# mt15_c.net
KiCad netlist of a schematic drawn in EAGLE
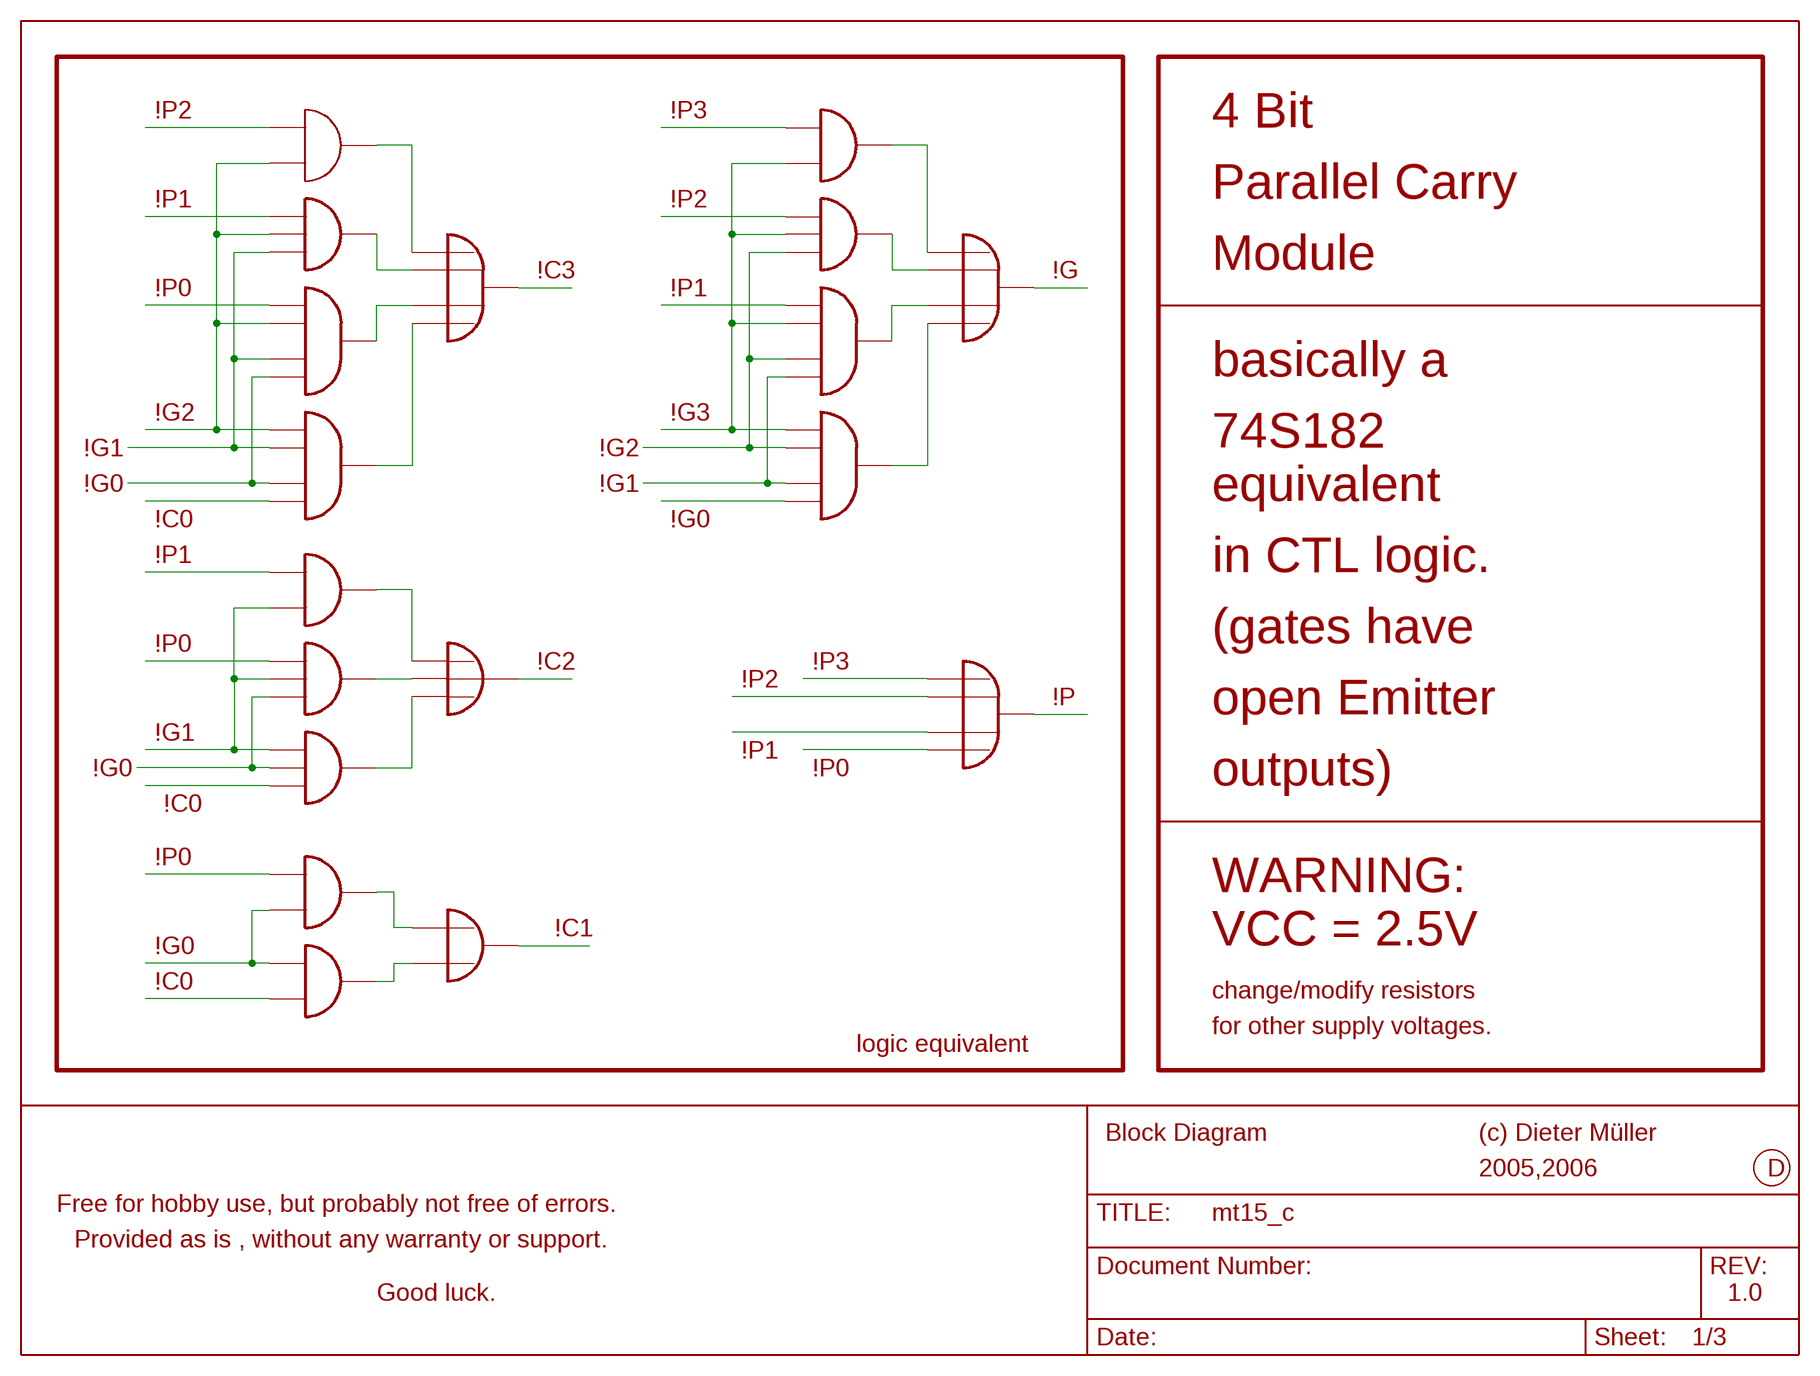
[diagram p0: schematic, sheet 1]
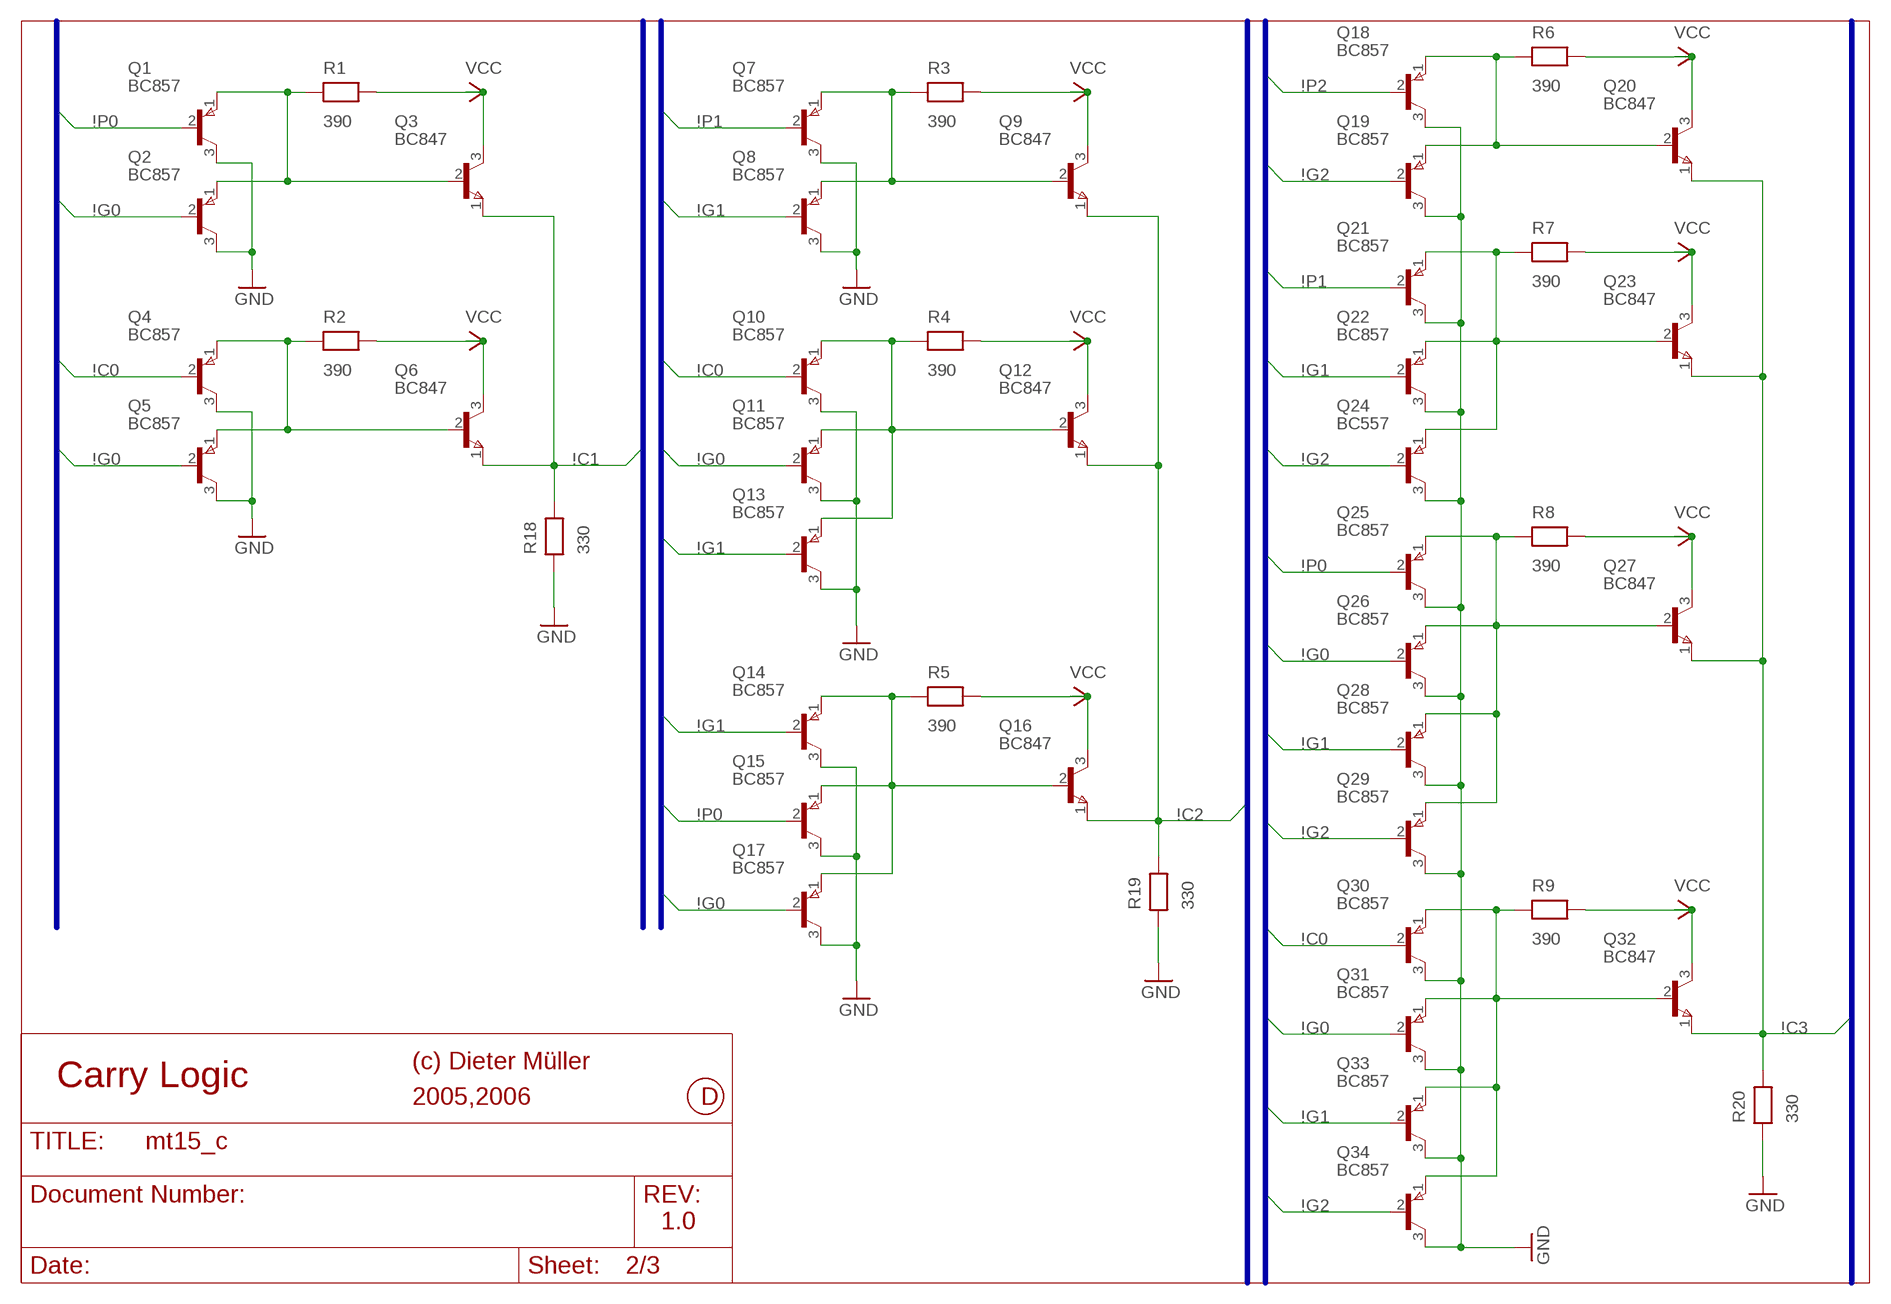
[diagram p1: schematic, sheet 2]
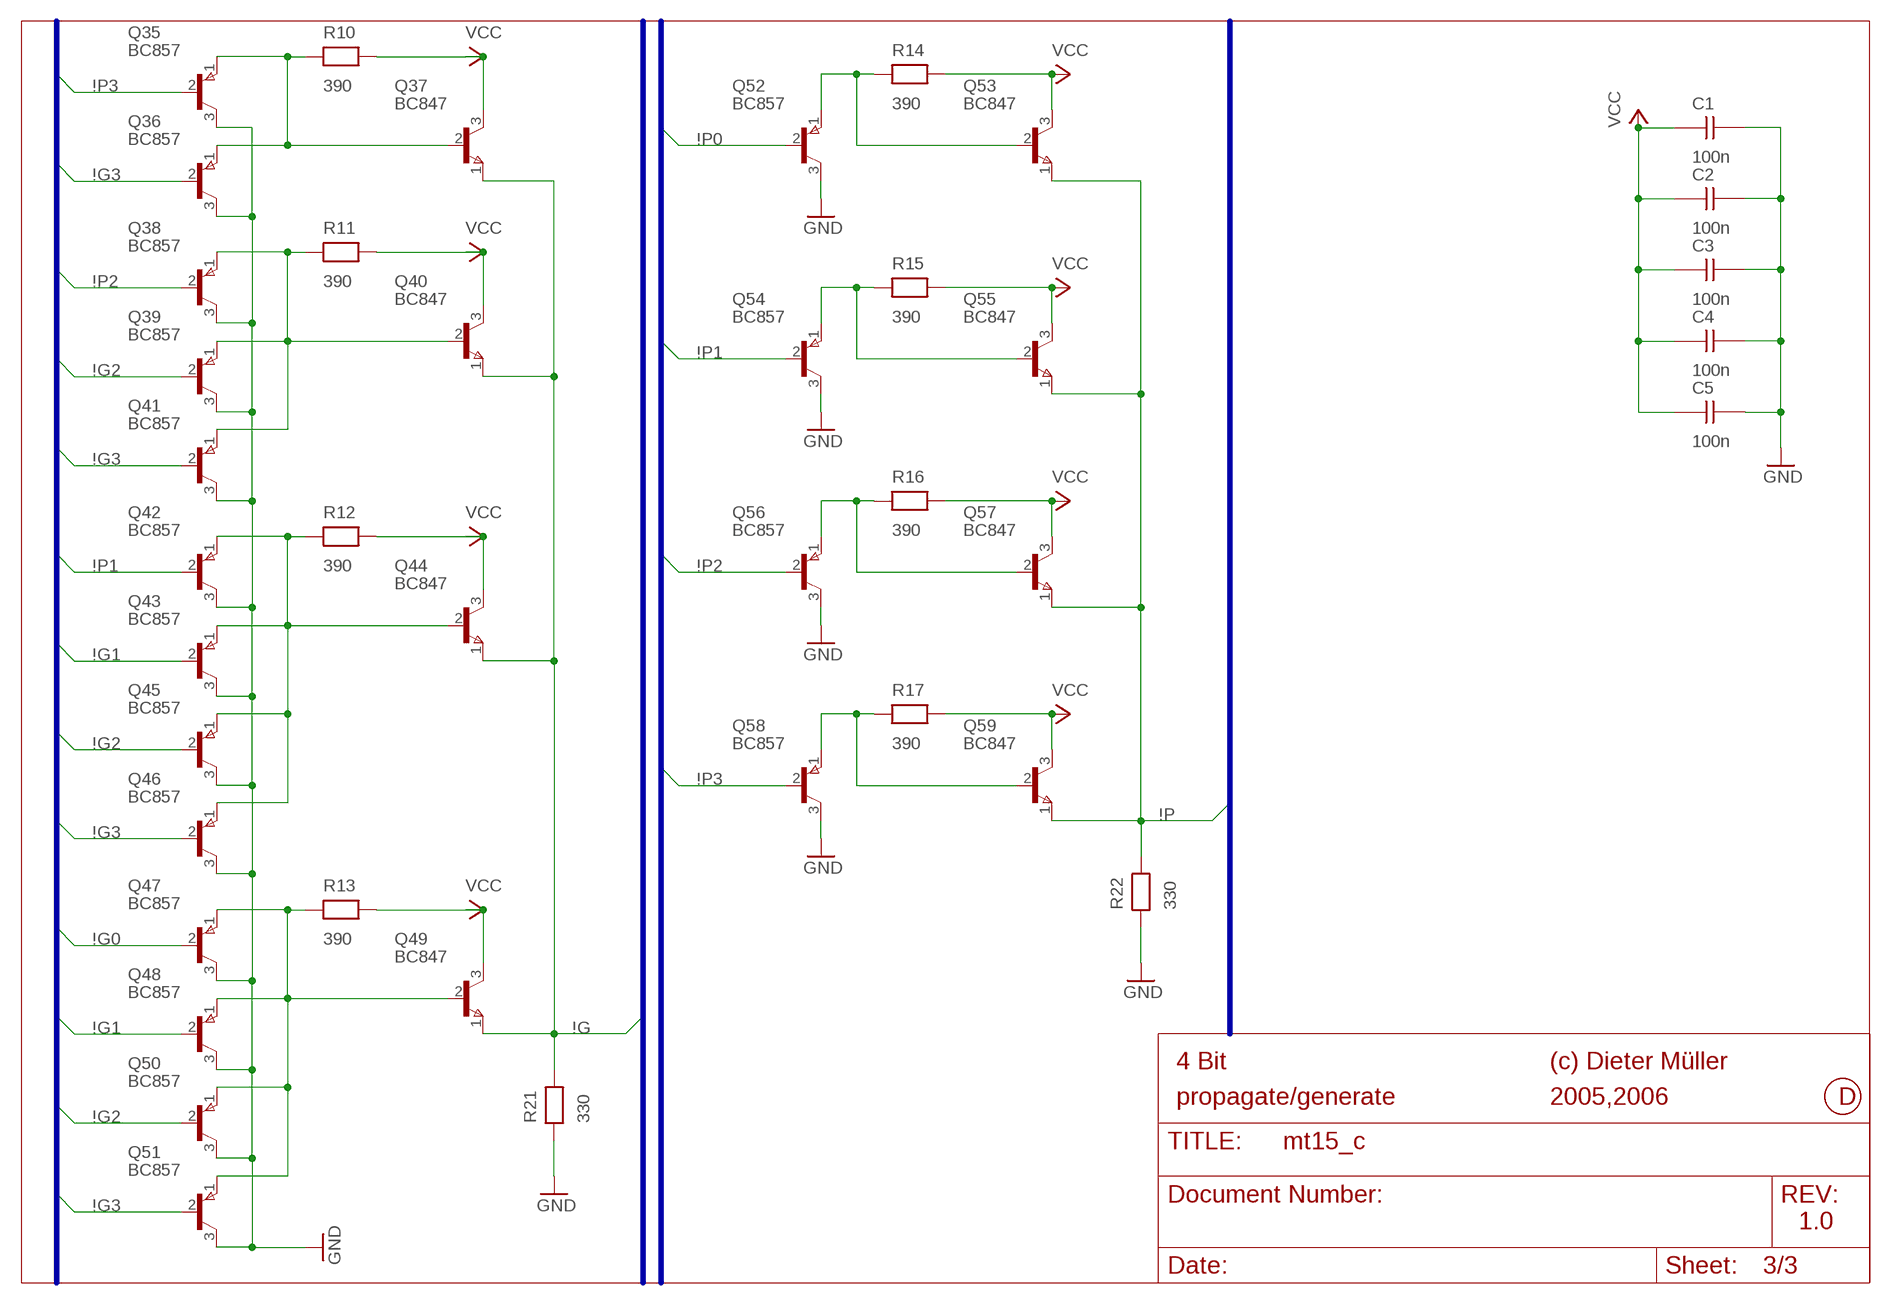
[diagram p2: schematic, sheet 3]

(export (version "E")
  (design (tool "Eeschema 10.0.6"))
  (components
    (comp (ref "Q1")
      (value "BC857")
      (footprint "eagle-import:SOT-23")
      (libsource (lib "eagle-import") (part "BC557@2"))
    )
    (comp (ref "Q2")
      (value "BC857")
      (footprint "eagle-import:SOT-23")
      (libsource (lib "eagle-import") (part "BC557@2"))
    )
    (comp (ref "Q3")
      (value "BC847")
      (footprint "eagle-import:SOT-23")
      (libsource (lib "eagle-import") (part "BC547@2"))
    )
    (comp (ref "Q4")
      (value "BC857")
      (footprint "eagle-import:SOT-23")
      (libsource (lib "eagle-import") (part "BC557@2"))
    )
    (comp (ref "Q5")
      (value "BC857")
      (footprint "eagle-import:SOT-23")
      (libsource (lib "eagle-import") (part "BC557@2"))
    )
    (comp (ref "Q6")
      (value "BC847")
      (footprint "eagle-import:SOT-23")
      (libsource (lib "eagle-import") (part "BC547@2"))
    )
    (comp (ref "Q7")
      (value "BC857")
      (footprint "eagle-import:SOT-23")
      (libsource (lib "eagle-import") (part "BC557@2"))
    )
    (comp (ref "Q8")
      (value "BC857")
      (footprint "eagle-import:SOT-23")
      (libsource (lib "eagle-import") (part "BC557@2"))
    )
    (comp (ref "Q9")
      (value "BC847")
      (footprint "eagle-import:SOT-23")
      (libsource (lib "eagle-import") (part "BC547@2"))
    )
    (comp (ref "Q10")
      (value "BC857")
      (footprint "eagle-import:SOT-23")
      (libsource (lib "eagle-import") (part "BC557@2"))
    )
    (comp (ref "Q11")
      (value "BC857")
      (footprint "eagle-import:SOT-23")
      (libsource (lib "eagle-import") (part "BC557@2"))
    )
    (comp (ref "Q12")
      (value "BC847")
      (footprint "eagle-import:SOT-23")
      (libsource (lib "eagle-import") (part "BC547@2"))
    )
    (comp (ref "Q13")
      (value "BC857")
      (footprint "eagle-import:SOT-23")
      (libsource (lib "eagle-import") (part "BC557@2"))
    )
    (comp (ref "Q14")
      (value "BC857")
      (footprint "eagle-import:SOT-23")
      (libsource (lib "eagle-import") (part "BC557@2"))
    )
    (comp (ref "Q15")
      (value "BC857")
      (footprint "eagle-import:SOT-23")
      (libsource (lib "eagle-import") (part "BC557@2"))
    )
    (comp (ref "Q16")
      (value "BC847")
      (footprint "eagle-import:SOT-23")
      (libsource (lib "eagle-import") (part "BC547@2"))
    )
    (comp (ref "Q17")
      (value "BC857")
      (footprint "eagle-import:SOT-23")
      (libsource (lib "eagle-import") (part "BC557@2"))
    )
    (comp (ref "Q18")
      (value "BC857")
      (footprint "eagle-import:SOT-23")
      (libsource (lib "eagle-import") (part "BC557@2"))
    )
    (comp (ref "Q19")
      (value "BC857")
      (footprint "eagle-import:SOT-23")
      (libsource (lib "eagle-import") (part "BC557@2"))
    )
    (comp (ref "Q20")
      (value "BC847")
      (footprint "eagle-import:SOT-23")
      (libsource (lib "eagle-import") (part "BC547@2"))
    )
    (comp (ref "Q21")
      (value "BC857")
      (footprint "eagle-import:SOT-23")
      (libsource (lib "eagle-import") (part "BC557@2"))
    )
    (comp (ref "Q22")
      (value "BC857")
      (footprint "eagle-import:SOT-23")
      (libsource (lib "eagle-import") (part "BC557@2"))
    )
    (comp (ref "Q23")
      (value "BC847")
      (footprint "eagle-import:SOT-23")
      (libsource (lib "eagle-import") (part "BC547@2"))
    )
    (comp (ref "Q24")
      (value "BC557")
      (footprint "eagle-import:SOT-23")
      (libsource (lib "eagle-import") (part "BC557@2"))
    )
    (comp (ref "Q25")
      (value "BC857")
      (footprint "eagle-import:SOT-23")
      (libsource (lib "eagle-import") (part "BC557@2"))
    )
    (comp (ref "Q26")
      (value "BC857")
      (footprint "eagle-import:SOT-23")
      (libsource (lib "eagle-import") (part "BC557@2"))
    )
    (comp (ref "Q27")
      (value "BC847")
      (footprint "eagle-import:SOT-23")
      (libsource (lib "eagle-import") (part "BC547@2"))
    )
    (comp (ref "Q28")
      (value "BC857")
      (footprint "eagle-import:SOT-23")
      (libsource (lib "eagle-import") (part "BC557@2"))
    )
    (comp (ref "Q29")
      (value "BC857")
      (footprint "eagle-import:SOT-23")
      (libsource (lib "eagle-import") (part "BC557@2"))
    )
    (comp (ref "Q30")
      (value "BC857")
      (footprint "eagle-import:SOT-23")
      (libsource (lib "eagle-import") (part "BC557@2"))
    )
    (comp (ref "Q31")
      (value "BC857")
      (footprint "eagle-import:SOT-23")
      (libsource (lib "eagle-import") (part "BC557@2"))
    )
    (comp (ref "Q32")
      (value "BC847")
      (footprint "eagle-import:SOT-23")
      (libsource (lib "eagle-import") (part "BC547@2"))
    )
    (comp (ref "Q33")
      (value "BC857")
      (footprint "eagle-import:SOT-23")
      (libsource (lib "eagle-import") (part "BC557@2"))
    )
    (comp (ref "Q34")
      (value "BC857")
      (footprint "eagle-import:SOT-23")
      (libsource (lib "eagle-import") (part "BC557@2"))
    )
    (comp (ref "R1")
      (value "390")
      (footprint "eagle-import:0204")
      (libsource (lib "eagle-import") (part "RESEU-7,5@2"))
    )
    (comp (ref "R2")
      (value "390")
      (footprint "eagle-import:0204")
      (libsource (lib "eagle-import") (part "RESEU-7,5@2"))
    )
    (comp (ref "R3")
      (value "390")
      (footprint "eagle-import:0204")
      (libsource (lib "eagle-import") (part "RESEU-7,5@2"))
    )
    (comp (ref "R4")
      (value "390")
      (footprint "eagle-import:0204")
      (libsource (lib "eagle-import") (part "RESEU-7,5@2"))
    )
    (comp (ref "R5")
      (value "390")
      (footprint "eagle-import:0204")
      (libsource (lib "eagle-import") (part "RESEU-7,5@2"))
    )
    (comp (ref "R6")
      (value "390")
      (footprint "eagle-import:0204")
      (libsource (lib "eagle-import") (part "RESEU-7,5@2"))
    )
    (comp (ref "R7")
      (value "390")
      (footprint "eagle-import:0204")
      (libsource (lib "eagle-import") (part "RESEU-7,5@2"))
    )
    (comp (ref "R8")
      (value "390")
      (footprint "eagle-import:0204")
      (libsource (lib "eagle-import") (part "RESEU-7,5@2"))
    )
    (comp (ref "R9")
      (value "390")
      (footprint "eagle-import:0204")
      (libsource (lib "eagle-import") (part "RESEU-7,5@2"))
    )
    (comp (ref "R18")
      (value "330")
      (footprint "eagle-import:0204")
      (libsource (lib "eagle-import") (part "RESEU-7,5@2"))
    )
    (comp (ref "R19")
      (value "330")
      (footprint "eagle-import:0204")
      (libsource (lib "eagle-import") (part "RESEU-7,5@2"))
    )
    (comp (ref "R20")
      (value "330")
      (footprint "eagle-import:0204")
      (libsource (lib "eagle-import") (part "RESEU-7,5@2"))
    )
    (comp (ref "C1")
      (value "100n")
      (footprint "eagle-import:0204")
      (libsource (lib "eagle-import") (part "CAPNP-5@2"))
    )
    (comp (ref "C2")
      (value "100n")
      (footprint "eagle-import:0204")
      (libsource (lib "eagle-import") (part "CAPNP-5@2"))
    )
    (comp (ref "C3")
      (value "100n")
      (footprint "eagle-import:0204")
      (libsource (lib "eagle-import") (part "CAPNP-5@2"))
    )
    (comp (ref "C4")
      (value "100n")
      (footprint "eagle-import:0204")
      (libsource (lib "eagle-import") (part "CAPNP-5@2"))
    )
    (comp (ref "C5")
      (value "100n")
      (footprint "eagle-import:0204")
      (libsource (lib "eagle-import") (part "CAPNP-5@2"))
    )
    (comp (ref "Q35")
      (value "BC857")
      (footprint "eagle-import:SOT-23")
      (libsource (lib "eagle-import") (part "BC557@2"))
    )
    (comp (ref "Q36")
      (value "BC857")
      (footprint "eagle-import:SOT-23")
      (libsource (lib "eagle-import") (part "BC557@2"))
    )
    (comp (ref "Q37")
      (value "BC847")
      (footprint "eagle-import:SOT-23")
      (libsource (lib "eagle-import") (part "BC547@2"))
    )
    (comp (ref "Q38")
      (value "BC857")
      (footprint "eagle-import:SOT-23")
      (libsource (lib "eagle-import") (part "BC557@2"))
    )
    (comp (ref "Q39")
      (value "BC857")
      (footprint "eagle-import:SOT-23")
      (libsource (lib "eagle-import") (part "BC557@2"))
    )
    (comp (ref "Q40")
      (value "BC847")
      (footprint "eagle-import:SOT-23")
      (libsource (lib "eagle-import") (part "BC547@2"))
    )
    (comp (ref "Q41")
      (value "BC857")
      (footprint "eagle-import:SOT-23")
      (libsource (lib "eagle-import") (part "BC557@2"))
    )
    (comp (ref "Q42")
      (value "BC857")
      (footprint "eagle-import:SOT-23")
      (libsource (lib "eagle-import") (part "BC557@2"))
    )
    (comp (ref "Q43")
      (value "BC857")
      (footprint "eagle-import:SOT-23")
      (libsource (lib "eagle-import") (part "BC557@2"))
    )
    (comp (ref "Q44")
      (value "BC847")
      (footprint "eagle-import:SOT-23")
      (libsource (lib "eagle-import") (part "BC547@2"))
    )
    (comp (ref "Q45")
      (value "BC857")
      (footprint "eagle-import:SOT-23")
      (libsource (lib "eagle-import") (part "BC557@2"))
    )
    (comp (ref "Q46")
      (value "BC857")
      (footprint "eagle-import:SOT-23")
      (libsource (lib "eagle-import") (part "BC557@2"))
    )
    (comp (ref "Q47")
      (value "BC857")
      (footprint "eagle-import:SOT-23")
      (libsource (lib "eagle-import") (part "BC557@2"))
    )
    (comp (ref "Q48")
      (value "BC857")
      (footprint "eagle-import:SOT-23")
      (libsource (lib "eagle-import") (part "BC557@2"))
    )
    (comp (ref "Q49")
      (value "BC847")
      (footprint "eagle-import:SOT-23")
      (libsource (lib "eagle-import") (part "BC547@2"))
    )
    (comp (ref "Q50")
      (value "BC857")
      (footprint "eagle-import:SOT-23")
      (libsource (lib "eagle-import") (part "BC557@2"))
    )
    (comp (ref "Q51")
      (value "BC857")
      (footprint "eagle-import:SOT-23")
      (libsource (lib "eagle-import") (part "BC557@2"))
    )
    (comp (ref "Q52")
      (value "BC857")
      (footprint "eagle-import:SOT-23")
      (libsource (lib "eagle-import") (part "BC557@2"))
    )
    (comp (ref "Q53")
      (value "BC847")
      (footprint "eagle-import:SOT-23")
      (libsource (lib "eagle-import") (part "BC547@2"))
    )
    (comp (ref "Q54")
      (value "BC857")
      (footprint "eagle-import:SOT-23")
      (libsource (lib "eagle-import") (part "BC557@2"))
    )
    (comp (ref "Q55")
      (value "BC847")
      (footprint "eagle-import:SOT-23")
      (libsource (lib "eagle-import") (part "BC547@2"))
    )
    (comp (ref "Q56")
      (value "BC857")
      (footprint "eagle-import:SOT-23")
      (libsource (lib "eagle-import") (part "BC557@2"))
    )
    (comp (ref "Q57")
      (value "BC847")
      (footprint "eagle-import:SOT-23")
      (libsource (lib "eagle-import") (part "BC547@2"))
    )
    (comp (ref "Q58")
      (value "BC857")
      (footprint "eagle-import:SOT-23")
      (libsource (lib "eagle-import") (part "BC557@2"))
    )
    (comp (ref "Q59")
      (value "BC847")
      (footprint "eagle-import:SOT-23")
      (libsource (lib "eagle-import") (part "BC547@2"))
    )
    (comp (ref "R10")
      (value "390")
      (footprint "eagle-import:0204")
      (libsource (lib "eagle-import") (part "RESEU-7,5@2"))
    )
    (comp (ref "R11")
      (value "390")
      (footprint "eagle-import:0204")
      (libsource (lib "eagle-import") (part "RESEU-7,5@2"))
    )
    (comp (ref "R12")
      (value "390")
      (footprint "eagle-import:0204")
      (libsource (lib "eagle-import") (part "RESEU-7,5@2"))
    )
    (comp (ref "R13")
      (value "390")
      (footprint "eagle-import:0204")
      (libsource (lib "eagle-import") (part "RESEU-7,5@2"))
    )
    (comp (ref "R14")
      (value "390")
      (footprint "eagle-import:0204")
      (libsource (lib "eagle-import") (part "RESEU-7,5@2"))
    )
    (comp (ref "R15")
      (value "390")
      (footprint "eagle-import:0204")
      (libsource (lib "eagle-import") (part "RESEU-7,5@2"))
    )
    (comp (ref "R16")
      (value "390")
      (footprint "eagle-import:0204")
      (libsource (lib "eagle-import") (part "RESEU-7,5@2"))
    )
    (comp (ref "R17")
      (value "390")
      (footprint "eagle-import:0204")
      (libsource (lib "eagle-import") (part "RESEU-7,5@2"))
    )
    (comp (ref "R21")
      (value "330")
      (footprint "eagle-import:0204")
      (libsource (lib "eagle-import") (part "RESEU-7,5@2"))
    )
    (comp (ref "R22")
      (value "330")
      (footprint "eagle-import:0204")
      (libsource (lib "eagle-import") (part "RESEU-7,5@2"))
    )
  )
  (nets
    (net (code "1") (name "GND") (class "Default")
      (node (ref "C1") (pin "2") (pinfunction "2_2") (pintype "passive"))
      (node (ref "C2") (pin "2") (pinfunction "2_2") (pintype "passive"))
      (node (ref "C3") (pin "2") (pinfunction "2_2") (pintype "passive"))
      (node (ref "C4") (pin "2") (pinfunction "2_2") (pintype "passive"))
      (node (ref "C5") (pin "2") (pinfunction "2_2") (pintype "passive"))
      (node (ref "Q1") (pin "3") (pinfunction "C_3") (pintype "passive"))
      (node (ref "Q10") (pin "3") (pinfunction "C_3") (pintype "passive"))
      (node (ref "Q11") (pin "3") (pinfunction "C_3") (pintype "passive"))
      (node (ref "Q13") (pin "3") (pinfunction "C_3") (pintype "passive"))
      (node (ref "Q14") (pin "3") (pinfunction "C_3") (pintype "passive"))
      (node (ref "Q15") (pin "3") (pinfunction "C_3") (pintype "passive"))
      (node (ref "Q17") (pin "3") (pinfunction "C_3") (pintype "passive"))
      (node (ref "Q18") (pin "3") (pinfunction "C_3") (pintype "passive"))
      (node (ref "Q19") (pin "3") (pinfunction "C_3") (pintype "passive"))
      (node (ref "Q2") (pin "3") (pinfunction "C_3") (pintype "passive"))
      (node (ref "Q21") (pin "3") (pinfunction "C_3") (pintype "passive"))
      (node (ref "Q22") (pin "3") (pinfunction "C_3") (pintype "passive"))
      (node (ref "Q24") (pin "3") (pinfunction "C_3") (pintype "passive"))
      (node (ref "Q25") (pin "3") (pinfunction "C_3") (pintype "passive"))
      (node (ref "Q26") (pin "3") (pinfunction "C_3") (pintype "passive"))
      (node (ref "Q28") (pin "3") (pinfunction "C_3") (pintype "passive"))
      (node (ref "Q29") (pin "3") (pinfunction "C_3") (pintype "passive"))
      (node (ref "Q30") (pin "3") (pinfunction "C_3") (pintype "passive"))
      (node (ref "Q31") (pin "3") (pinfunction "C_3") (pintype "passive"))
      (node (ref "Q33") (pin "3") (pinfunction "C_3") (pintype "passive"))
      (node (ref "Q34") (pin "3") (pinfunction "C_3") (pintype "passive"))
      (node (ref "Q35") (pin "3") (pinfunction "C_3") (pintype "passive"))
      (node (ref "Q36") (pin "3") (pinfunction "C_3") (pintype "passive"))
      (node (ref "Q38") (pin "3") (pinfunction "C_3") (pintype "passive"))
      (node (ref "Q39") (pin "3") (pinfunction "C_3") (pintype "passive"))
      (node (ref "Q4") (pin "3") (pinfunction "C_3") (pintype "passive"))
      (node (ref "Q41") (pin "3") (pinfunction "C_3") (pintype "passive"))
      (node (ref "Q42") (pin "3") (pinfunction "C_3") (pintype "passive"))
      (node (ref "Q43") (pin "3") (pinfunction "C_3") (pintype "passive"))
      (node (ref "Q45") (pin "3") (pinfunction "C_3") (pintype "passive"))
      (node (ref "Q46") (pin "3") (pinfunction "C_3") (pintype "passive"))
      (node (ref "Q47") (pin "3") (pinfunction "C_3") (pintype "passive"))
      (node (ref "Q48") (pin "3") (pinfunction "C_3") (pintype "passive"))
      (node (ref "Q5") (pin "3") (pinfunction "C_3") (pintype "passive"))
      (node (ref "Q50") (pin "3") (pinfunction "C_3") (pintype "passive"))
      (node (ref "Q51") (pin "3") (pinfunction "C_3") (pintype "passive"))
      (node (ref "Q52") (pin "3") (pinfunction "C_3") (pintype "passive"))
      (node (ref "Q54") (pin "3") (pinfunction "C_3") (pintype "passive"))
      (node (ref "Q56") (pin "3") (pinfunction "C_3") (pintype "passive"))
      (node (ref "Q58") (pin "3") (pinfunction "C_3") (pintype "passive"))
      (node (ref "Q7") (pin "3") (pinfunction "C_3") (pintype "passive"))
      (node (ref "Q8") (pin "3") (pinfunction "C_3") (pintype "passive"))
      (node (ref "R18") (pin "1") (pinfunction "1_1") (pintype "passive"))
      (node (ref "R19") (pin "1") (pinfunction "1_1") (pintype "passive"))
      (node (ref "R20") (pin "1") (pinfunction "1_1") (pintype "passive"))
      (node (ref "R21") (pin "1") (pinfunction "1_1") (pintype "passive"))
      (node (ref "R22") (pin "1") (pinfunction "1_1") (pintype "passive"))
    )
    (net (code "2") (name "Net-(Q1-E)") (class "Default")
      (node (ref "Q1") (pin "1") (pinfunction "E_1") (pintype "passive"))
      (node (ref "Q2") (pin "1") (pinfunction "E_1") (pintype "passive"))
      (node (ref "Q3") (pin "2") (pinfunction "B_2") (pintype "passive"))
      (node (ref "R1") (pin "1") (pinfunction "1_1") (pintype "passive"))
    )
    (net (code "3") (name "Net-(Q4-E)") (class "Default")
      (node (ref "Q4") (pin "1") (pinfunction "E_1") (pintype "passive"))
      (node (ref "Q5") (pin "1") (pinfunction "E_1") (pintype "passive"))
      (node (ref "Q6") (pin "2") (pinfunction "B_2") (pintype "passive"))
      (node (ref "R2") (pin "1") (pinfunction "1_1") (pintype "passive"))
    )
    (net (code "4") (name "Net-(Q7-E)") (class "Default")
      (node (ref "Q7") (pin "1") (pinfunction "E_1") (pintype "passive"))
      (node (ref "Q8") (pin "1") (pinfunction "E_1") (pintype "passive"))
      (node (ref "Q9") (pin "2") (pinfunction "B_2") (pintype "passive"))
      (node (ref "R3") (pin "1") (pinfunction "1_1") (pintype "passive"))
    )
    (net (code "5") (name "Net-(Q10-E)") (class "Default")
      (node (ref "Q10") (pin "1") (pinfunction "E_1") (pintype "passive"))
      (node (ref "Q11") (pin "1") (pinfunction "E_1") (pintype "passive"))
      (node (ref "Q12") (pin "2") (pinfunction "B_2") (pintype "passive"))
      (node (ref "Q13") (pin "1") (pinfunction "E_1") (pintype "passive"))
      (node (ref "R4") (pin "1") (pinfunction "1_1") (pintype "passive"))
    )
    (net (code "6") (name "Net-(Q14-E)") (class "Default")
      (node (ref "Q14") (pin "1") (pinfunction "E_1") (pintype "passive"))
      (node (ref "Q15") (pin "1") (pinfunction "E_1") (pintype "passive"))
      (node (ref "Q16") (pin "2") (pinfunction "B_2") (pintype "passive"))
      (node (ref "Q17") (pin "1") (pinfunction "E_1") (pintype "passive"))
      (node (ref "R5") (pin "1") (pinfunction "1_1") (pintype "passive"))
    )
    (net (code "7") (name "Net-(Q18-E)") (class "Default")
      (node (ref "Q18") (pin "1") (pinfunction "E_1") (pintype "passive"))
      (node (ref "Q19") (pin "1") (pinfunction "E_1") (pintype "passive"))
      (node (ref "Q20") (pin "2") (pinfunction "B_2") (pintype "passive"))
      (node (ref "R6") (pin "1") (pinfunction "1_1") (pintype "passive"))
    )
    (net (code "8") (name "Net-(Q21-E)") (class "Default")
      (node (ref "Q21") (pin "1") (pinfunction "E_1") (pintype "passive"))
      (node (ref "Q22") (pin "1") (pinfunction "E_1") (pintype "passive"))
      (node (ref "Q23") (pin "2") (pinfunction "B_2") (pintype "passive"))
      (node (ref "Q24") (pin "1") (pinfunction "E_1") (pintype "passive"))
      (node (ref "R7") (pin "1") (pinfunction "1_1") (pintype "passive"))
    )
    (net (code "9") (name "Net-(Q25-E)") (class "Default")
      (node (ref "Q25") (pin "1") (pinfunction "E_1") (pintype "passive"))
      (node (ref "Q26") (pin "1") (pinfunction "E_1") (pintype "passive"))
      (node (ref "Q27") (pin "2") (pinfunction "B_2") (pintype "passive"))
      (node (ref "Q28") (pin "1") (pinfunction "E_1") (pintype "passive"))
      (node (ref "Q29") (pin "1") (pinfunction "E_1") (pintype "passive"))
      (node (ref "R8") (pin "1") (pinfunction "1_1") (pintype "passive"))
    )
    (net (code "10") (name "Net-(Q30-E)") (class "Default")
      (node (ref "Q30") (pin "1") (pinfunction "E_1") (pintype "passive"))
      (node (ref "Q31") (pin "1") (pinfunction "E_1") (pintype "passive"))
      (node (ref "Q32") (pin "2") (pinfunction "B_2") (pintype "passive"))
      (node (ref "Q33") (pin "1") (pinfunction "E_1") (pintype "passive"))
      (node (ref "Q34") (pin "1") (pinfunction "E_1") (pintype "passive"))
      (node (ref "R9") (pin "1") (pinfunction "1_1") (pintype "passive"))
    )
    (net (code "11") (name "Net-(Q35-E)") (class "Default")
      (node (ref "Q35") (pin "1") (pinfunction "E_1") (pintype "passive"))
      (node (ref "Q36") (pin "1") (pinfunction "E_1") (pintype "passive"))
      (node (ref "Q37") (pin "2") (pinfunction "B_2") (pintype "passive"))
      (node (ref "R10") (pin "1") (pinfunction "1_1") (pintype "passive"))
    )
    (net (code "12") (name "Net-(Q38-E)") (class "Default")
      (node (ref "Q38") (pin "1") (pinfunction "E_1") (pintype "passive"))
      (node (ref "Q39") (pin "1") (pinfunction "E_1") (pintype "passive"))
      (node (ref "Q40") (pin "2") (pinfunction "B_2") (pintype "passive"))
      (node (ref "Q41") (pin "1") (pinfunction "E_1") (pintype "passive"))
      (node (ref "R11") (pin "1") (pinfunction "1_1") (pintype "passive"))
    )
    (net (code "13") (name "Net-(Q42-E)") (class "Default")
      (node (ref "Q42") (pin "1") (pinfunction "E_1") (pintype "passive"))
      (node (ref "Q43") (pin "1") (pinfunction "E_1") (pintype "passive"))
      (node (ref "Q44") (pin "2") (pinfunction "B_2") (pintype "passive"))
      (node (ref "Q45") (pin "1") (pinfunction "E_1") (pintype "passive"))
      (node (ref "Q46") (pin "1") (pinfunction "E_1") (pintype "passive"))
      (node (ref "R12") (pin "1") (pinfunction "1_1") (pintype "passive"))
    )
    (net (code "14") (name "Net-(Q47-E)") (class "Default")
      (node (ref "Q47") (pin "1") (pinfunction "E_1") (pintype "passive"))
      (node (ref "Q48") (pin "1") (pinfunction "E_1") (pintype "passive"))
      (node (ref "Q49") (pin "2") (pinfunction "B_2") (pintype "passive"))
      (node (ref "Q50") (pin "1") (pinfunction "E_1") (pintype "passive"))
      (node (ref "Q51") (pin "1") (pinfunction "E_1") (pintype "passive"))
      (node (ref "R13") (pin "1") (pinfunction "1_1") (pintype "passive"))
    )
    (net (code "15") (name "Net-(Q52-E)") (class "Default")
      (node (ref "Q52") (pin "1") (pinfunction "E_1") (pintype "passive"))
      (node (ref "Q53") (pin "2") (pinfunction "B_2") (pintype "passive"))
      (node (ref "R14") (pin "1") (pinfunction "1_1") (pintype "passive"))
    )
    (net (code "16") (name "Net-(Q54-E)") (class "Default")
      (node (ref "Q54") (pin "1") (pinfunction "E_1") (pintype "passive"))
      (node (ref "Q55") (pin "2") (pinfunction "B_2") (pintype "passive"))
      (node (ref "R15") (pin "1") (pinfunction "1_1") (pintype "passive"))
    )
    (net (code "17") (name "Net-(Q56-E)") (class "Default")
      (node (ref "Q56") (pin "1") (pinfunction "E_1") (pintype "passive"))
      (node (ref "Q57") (pin "2") (pinfunction "B_2") (pintype "passive"))
      (node (ref "R16") (pin "1") (pinfunction "1_1") (pintype "passive"))
    )
    (net (code "18") (name "Net-(Q58-E)") (class "Default")
      (node (ref "Q58") (pin "1") (pinfunction "E_1") (pintype "passive"))
      (node (ref "Q59") (pin "2") (pinfunction "B_2") (pintype "passive"))
      (node (ref "R17") (pin "1") (pinfunction "1_1") (pintype "passive"))
    )
    (net (code "19") (name "VCC") (class "Default")
      (node (ref "C1") (pin "1") (pinfunction "1_1") (pintype "passive"))
      (node (ref "C2") (pin "1") (pinfunction "1_1") (pintype "passive"))
      (node (ref "C3") (pin "1") (pinfunction "1_1") (pintype "passive"))
      (node (ref "C4") (pin "1") (pinfunction "1_1") (pintype "passive"))
      (node (ref "C5") (pin "1") (pinfunction "1_1") (pintype "passive"))
      (node (ref "Q12") (pin "3") (pinfunction "C_3") (pintype "passive"))
      (node (ref "Q16") (pin "3") (pinfunction "C_3") (pintype "passive"))
      (node (ref "Q20") (pin "3") (pinfunction "C_3") (pintype "passive"))
      (node (ref "Q23") (pin "3") (pinfunction "C_3") (pintype "passive"))
      (node (ref "Q27") (pin "3") (pinfunction "C_3") (pintype "passive"))
      (node (ref "Q3") (pin "3") (pinfunction "C_3") (pintype "passive"))
      (node (ref "Q32") (pin "3") (pinfunction "C_3") (pintype "passive"))
      (node (ref "Q37") (pin "3") (pinfunction "C_3") (pintype "passive"))
      (node (ref "Q40") (pin "3") (pinfunction "C_3") (pintype "passive"))
      (node (ref "Q44") (pin "3") (pinfunction "C_3") (pintype "passive"))
      (node (ref "Q49") (pin "3") (pinfunction "C_3") (pintype "passive"))
      (node (ref "Q53") (pin "3") (pinfunction "C_3") (pintype "passive"))
      (node (ref "Q55") (pin "3") (pinfunction "C_3") (pintype "passive"))
      (node (ref "Q57") (pin "3") (pinfunction "C_3") (pintype "passive"))
      (node (ref "Q59") (pin "3") (pinfunction "C_3") (pintype "passive"))
      (node (ref "Q6") (pin "3") (pinfunction "C_3") (pintype "passive"))
      (node (ref "Q9") (pin "3") (pinfunction "C_3") (pintype "passive"))
      (node (ref "R1") (pin "2") (pinfunction "2_2") (pintype "passive"))
      (node (ref "R10") (pin "2") (pinfunction "2_2") (pintype "passive"))
      (node (ref "R11") (pin "2") (pinfunction "2_2") (pintype "passive"))
      (node (ref "R12") (pin "2") (pinfunction "2_2") (pintype "passive"))
      (node (ref "R13") (pin "2") (pinfunction "2_2") (pintype "passive"))
      (node (ref "R14") (pin "2") (pinfunction "2_2") (pintype "passive"))
      (node (ref "R15") (pin "2") (pinfunction "2_2") (pintype "passive"))
      (node (ref "R16") (pin "2") (pinfunction "2_2") (pintype "passive"))
      (node (ref "R17") (pin "2") (pinfunction "2_2") (pintype "passive"))
      (node (ref "R2") (pin "2") (pinfunction "2_2") (pintype "passive"))
      (node (ref "R3") (pin "2") (pinfunction "2_2") (pintype "passive"))
      (node (ref "R4") (pin "2") (pinfunction "2_2") (pintype "passive"))
      (node (ref "R5") (pin "2") (pinfunction "2_2") (pintype "passive"))
      (node (ref "R6") (pin "2") (pinfunction "2_2") (pintype "passive"))
      (node (ref "R7") (pin "2") (pinfunction "2_2") (pintype "passive"))
      (node (ref "R8") (pin "2") (pinfunction "2_2") (pintype "passive"))
      (node (ref "R9") (pin "2") (pinfunction "2_2") (pintype "passive"))
    )
    (net (code "20") (name "\\~{C0}") (class "Default")
      (node (ref "Q10") (pin "2") (pinfunction "B_2") (pintype "passive"))
      (node (ref "Q30") (pin "2") (pinfunction "B_2") (pintype "passive"))
      (node (ref "Q4") (pin "2") (pinfunction "B_2") (pintype "passive"))
    )
    (net (code "21") (name "\\~{C1}") (class "Default")
      (node (ref "Q3") (pin "1") (pinfunction "E_1") (pintype "passive"))
      (node (ref "Q6") (pin "1") (pinfunction "E_1") (pintype "passive"))
      (node (ref "R18") (pin "2") (pinfunction "2_2") (pintype "passive"))
    )
    (net (code "22") (name "\\~{C2}") (class "Default")
      (node (ref "Q12") (pin "1") (pinfunction "E_1") (pintype "passive"))
      (node (ref "Q16") (pin "1") (pinfunction "E_1") (pintype "passive"))
      (node (ref "Q9") (pin "1") (pinfunction "E_1") (pintype "passive"))
      (node (ref "R19") (pin "2") (pinfunction "2_2") (pintype "passive"))
    )
    (net (code "23") (name "\\~{C3}") (class "Default")
      (node (ref "Q20") (pin "1") (pinfunction "E_1") (pintype "passive"))
      (node (ref "Q23") (pin "1") (pinfunction "E_1") (pintype "passive"))
      (node (ref "Q27") (pin "1") (pinfunction "E_1") (pintype "passive"))
      (node (ref "Q32") (pin "1") (pinfunction "E_1") (pintype "passive"))
      (node (ref "R20") (pin "2") (pinfunction "2_2") (pintype "passive"))
    )
    (net (code "24") (name "\\~{G0}") (class "Default")
      (node (ref "Q11") (pin "2") (pinfunction "B_2") (pintype "passive"))
      (node (ref "Q17") (pin "2") (pinfunction "B_2") (pintype "passive"))
      (node (ref "Q2") (pin "2") (pinfunction "B_2") (pintype "passive"))
      (node (ref "Q26") (pin "2") (pinfunction "B_2") (pintype "passive"))
      (node (ref "Q31") (pin "2") (pinfunction "B_2") (pintype "passive"))
      (node (ref "Q47") (pin "2") (pinfunction "B_2") (pintype "passive"))
      (node (ref "Q5") (pin "2") (pinfunction "B_2") (pintype "passive"))
    )
    (net (code "25") (name "\\~{G1}") (class "Default")
      (node (ref "Q13") (pin "2") (pinfunction "B_2") (pintype "passive"))
      (node (ref "Q14") (pin "2") (pinfunction "B_2") (pintype "passive"))
      (node (ref "Q22") (pin "2") (pinfunction "B_2") (pintype "passive"))
      (node (ref "Q28") (pin "2") (pinfunction "B_2") (pintype "passive"))
      (node (ref "Q33") (pin "2") (pinfunction "B_2") (pintype "passive"))
      (node (ref "Q43") (pin "2") (pinfunction "B_2") (pintype "passive"))
      (node (ref "Q48") (pin "2") (pinfunction "B_2") (pintype "passive"))
      (node (ref "Q8") (pin "2") (pinfunction "B_2") (pintype "passive"))
    )
    (net (code "26") (name "\\~{G2}") (class "Default")
      (node (ref "Q19") (pin "2") (pinfunction "B_2") (pintype "passive"))
      (node (ref "Q24") (pin "2") (pinfunction "B_2") (pintype "passive"))
      (node (ref "Q29") (pin "2") (pinfunction "B_2") (pintype "passive"))
      (node (ref "Q34") (pin "2") (pinfunction "B_2") (pintype "passive"))
      (node (ref "Q39") (pin "2") (pinfunction "B_2") (pintype "passive"))
      (node (ref "Q45") (pin "2") (pinfunction "B_2") (pintype "passive"))
      (node (ref "Q50") (pin "2") (pinfunction "B_2") (pintype "passive"))
    )
    (net (code "27") (name "\\~{G3}") (class "Default")
      (node (ref "Q36") (pin "2") (pinfunction "B_2") (pintype "passive"))
      (node (ref "Q41") (pin "2") (pinfunction "B_2") (pintype "passive"))
      (node (ref "Q46") (pin "2") (pinfunction "B_2") (pintype "passive"))
      (node (ref "Q51") (pin "2") (pinfunction "B_2") (pintype "passive"))
    )
    (net (code "28") (name "\\~{G}") (class "Default")
      (node (ref "Q37") (pin "1") (pinfunction "E_1") (pintype "passive"))
      (node (ref "Q40") (pin "1") (pinfunction "E_1") (pintype "passive"))
      (node (ref "Q44") (pin "1") (pinfunction "E_1") (pintype "passive"))
      (node (ref "Q49") (pin "1") (pinfunction "E_1") (pintype "passive"))
      (node (ref "R21") (pin "2") (pinfunction "2_2") (pintype "passive"))
    )
    (net (code "29") (name "\\~{P0}") (class "Default")
      (node (ref "Q1") (pin "2") (pinfunction "B_2") (pintype "passive"))
      (node (ref "Q15") (pin "2") (pinfunction "B_2") (pintype "passive"))
      (node (ref "Q25") (pin "2") (pinfunction "B_2") (pintype "passive"))
      (node (ref "Q52") (pin "2") (pinfunction "B_2") (pintype "passive"))
    )
    (net (code "30") (name "\\~{P1}") (class "Default")
      (node (ref "Q21") (pin "2") (pinfunction "B_2") (pintype "passive"))
      (node (ref "Q42") (pin "2") (pinfunction "B_2") (pintype "passive"))
      (node (ref "Q54") (pin "2") (pinfunction "B_2") (pintype "passive"))
      (node (ref "Q7") (pin "2") (pinfunction "B_2") (pintype "passive"))
    )
    (net (code "31") (name "\\~{P2}") (class "Default")
      (node (ref "Q18") (pin "2") (pinfunction "B_2") (pintype "passive"))
      (node (ref "Q38") (pin "2") (pinfunction "B_2") (pintype "passive"))
      (node (ref "Q56") (pin "2") (pinfunction "B_2") (pintype "passive"))
    )
    (net (code "32") (name "\\~{P3}") (class "Default")
      (node (ref "Q35") (pin "2") (pinfunction "B_2") (pintype "passive"))
      (node (ref "Q58") (pin "2") (pinfunction "B_2") (pintype "passive"))
    )
    (net (code "33") (name "\\~{P}") (class "Default")
      (node (ref "Q53") (pin "1") (pinfunction "E_1") (pintype "passive"))
      (node (ref "Q55") (pin "1") (pinfunction "E_1") (pintype "passive"))
      (node (ref "Q57") (pin "1") (pinfunction "E_1") (pintype "passive"))
      (node (ref "Q59") (pin "1") (pinfunction "E_1") (pintype "passive"))
      (node (ref "R22") (pin "2") (pinfunction "2_2") (pintype "passive"))
    )
  )
)
